# clk_gate.net
KiCad netlist of a schematic drawn in EAGLE
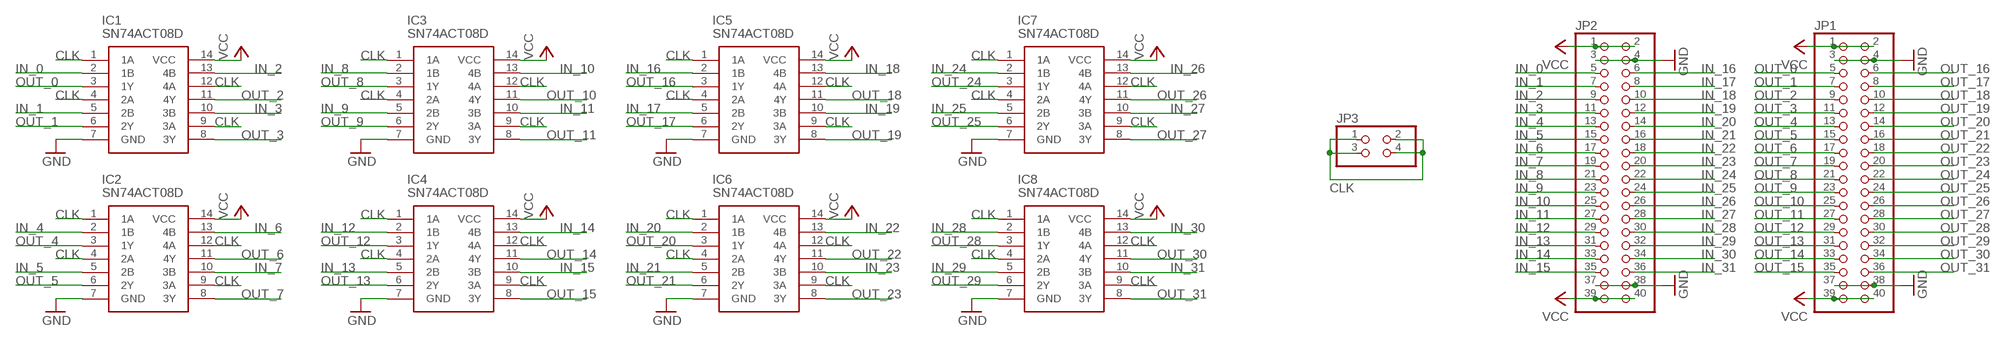
[diagram p0: schematic, sheet 1]

(export (version "E")
  (design (tool "Eeschema 10.0.6"))
  (components
    (comp (ref "IC1")
      (value "SN74ACT08D")
      (footprint "eagle-import:SOIC127P600X175-14N")
      (fields (field (name "MOUSER_PART_NUMBER") "595-SN74ACT08D"))
      (libsource (lib "eagle-import") (part "SN74ACT08D"))
    )
    (comp (ref "IC2")
      (value "SN74ACT08D")
      (footprint "eagle-import:SOIC127P600X175-14N")
      (fields (field (name "MOUSER_PART_NUMBER") "595-SN74ACT08D"))
      (libsource (lib "eagle-import") (part "SN74ACT08D"))
    )
    (comp (ref "IC3")
      (value "SN74ACT08D")
      (footprint "eagle-import:SOIC127P600X175-14N")
      (fields (field (name "MOUSER_PART_NUMBER") "595-SN74ACT08D"))
      (libsource (lib "eagle-import") (part "SN74ACT08D"))
    )
    (comp (ref "IC4")
      (value "SN74ACT08D")
      (footprint "eagle-import:SOIC127P600X175-14N")
      (fields (field (name "MOUSER_PART_NUMBER") "595-SN74ACT08D"))
      (libsource (lib "eagle-import") (part "SN74ACT08D"))
    )
    (comp (ref "IC5")
      (value "SN74ACT08D")
      (footprint "eagle-import:SOIC127P600X175-14N")
      (fields (field (name "MOUSER_PART_NUMBER") "595-SN74ACT08D"))
      (libsource (lib "eagle-import") (part "SN74ACT08D"))
    )
    (comp (ref "IC6")
      (value "SN74ACT08D")
      (footprint "eagle-import:SOIC127P600X175-14N")
      (fields (field (name "MOUSER_PART_NUMBER") "595-SN74ACT08D"))
      (libsource (lib "eagle-import") (part "SN74ACT08D"))
    )
    (comp (ref "IC7")
      (value "SN74ACT08D")
      (footprint "eagle-import:SOIC127P600X175-14N")
      (fields (field (name "MOUSER_PART_NUMBER") "595-SN74ACT08D"))
      (libsource (lib "eagle-import") (part "SN74ACT08D"))
    )
    (comp (ref "IC8")
      (value "SN74ACT08D")
      (footprint "eagle-import:SOIC127P600X175-14N")
      (fields (field (name "MOUSER_PART_NUMBER") "595-SN74ACT08D"))
      (libsource (lib "eagle-import") (part "SN74ACT08D"))
    )
    (comp (ref "JP1")
      (value "PINHD-2X20")
      (footprint "eagle-import:2X20")
      (libsource (lib "eagle-import") (part "PINHD-2X20"))
    )
    (comp (ref "JP2")
      (value "PINHD-2X20")
      (footprint "eagle-import:2X20")
      (libsource (lib "eagle-import") (part "PINHD-2X20"))
    )
    (comp (ref "JP3")
      (value "PINHD-2X2")
      (footprint "eagle-import:2X02")
      (libsource (lib "eagle-import") (part "PINHD-2X2"))
    )
  )
  (nets
    (net (code "1") (name "/CLK") (class "Default")
      (node (ref "IC1") (pin "1") (pinfunction "1A_1") (pintype "bidirectional"))
      (node (ref "IC1") (pin "12") (pinfunction "4A_12") (pintype "bidirectional"))
      (node (ref "IC1") (pin "4") (pinfunction "2A_4") (pintype "bidirectional"))
      (node (ref "IC1") (pin "9") (pinfunction "3A_9") (pintype "bidirectional"))
      (node (ref "IC2") (pin "1") (pinfunction "1A_1") (pintype "bidirectional"))
      (node (ref "IC2") (pin "12") (pinfunction "4A_12") (pintype "bidirectional"))
      (node (ref "IC2") (pin "4") (pinfunction "2A_4") (pintype "bidirectional"))
      (node (ref "IC2") (pin "9") (pinfunction "3A_9") (pintype "bidirectional"))
      (node (ref "IC3") (pin "1") (pinfunction "1A_1") (pintype "bidirectional"))
      (node (ref "IC3") (pin "12") (pinfunction "4A_12") (pintype "bidirectional"))
      (node (ref "IC3") (pin "4") (pinfunction "2A_4") (pintype "bidirectional"))
      (node (ref "IC3") (pin "9") (pinfunction "3A_9") (pintype "bidirectional"))
      (node (ref "IC4") (pin "1") (pinfunction "1A_1") (pintype "bidirectional"))
      (node (ref "IC4") (pin "12") (pinfunction "4A_12") (pintype "bidirectional"))
      (node (ref "IC4") (pin "4") (pinfunction "2A_4") (pintype "bidirectional"))
      (node (ref "IC4") (pin "9") (pinfunction "3A_9") (pintype "bidirectional"))
      (node (ref "IC5") (pin "1") (pinfunction "1A_1") (pintype "bidirectional"))
      (node (ref "IC5") (pin "12") (pinfunction "4A_12") (pintype "bidirectional"))
      (node (ref "IC5") (pin "4") (pinfunction "2A_4") (pintype "bidirectional"))
      (node (ref "IC5") (pin "9") (pinfunction "3A_9") (pintype "bidirectional"))
      (node (ref "IC6") (pin "1") (pinfunction "1A_1") (pintype "bidirectional"))
      (node (ref "IC6") (pin "12") (pinfunction "4A_12") (pintype "bidirectional"))
      (node (ref "IC6") (pin "4") (pinfunction "2A_4") (pintype "bidirectional"))
      (node (ref "IC6") (pin "9") (pinfunction "3A_9") (pintype "bidirectional"))
      (node (ref "IC7") (pin "1") (pinfunction "1A_1") (pintype "bidirectional"))
      (node (ref "IC7") (pin "12") (pinfunction "4A_12") (pintype "bidirectional"))
      (node (ref "IC7") (pin "4") (pinfunction "2A_4") (pintype "bidirectional"))
      (node (ref "IC7") (pin "9") (pinfunction "3A_9") (pintype "bidirectional"))
      (node (ref "IC8") (pin "1") (pinfunction "1A_1") (pintype "bidirectional"))
      (node (ref "IC8") (pin "12") (pinfunction "4A_12") (pintype "bidirectional"))
      (node (ref "IC8") (pin "4") (pinfunction "2A_4") (pintype "bidirectional"))
      (node (ref "IC8") (pin "9") (pinfunction "3A_9") (pintype "bidirectional"))
      (node (ref "JP3") (pin "1") (pinfunction "1_1") (pintype "passive"))
      (node (ref "JP3") (pin "2") (pinfunction "2_2") (pintype "passive"))
      (node (ref "JP3") (pin "3") (pinfunction "3_3") (pintype "passive"))
      (node (ref "JP3") (pin "4") (pinfunction "4_4") (pintype "passive"))
    )
    (net (code "2") (name "/IN_0") (class "Default")
      (node (ref "IC1") (pin "2") (pinfunction "1B_2") (pintype "bidirectional"))
      (node (ref "JP2") (pin "5") (pinfunction "5_5") (pintype "passive"))
    )
    (net (code "3") (name "/IN_1") (class "Default")
      (node (ref "IC1") (pin "5") (pinfunction "2B_5") (pintype "bidirectional"))
      (node (ref "JP2") (pin "7") (pinfunction "7_7") (pintype "passive"))
    )
    (net (code "4") (name "/IN_2") (class "Default")
      (node (ref "IC1") (pin "13") (pinfunction "4B_13") (pintype "bidirectional"))
      (node (ref "JP2") (pin "9") (pinfunction "9_9") (pintype "passive"))
    )
    (net (code "5") (name "/IN_3") (class "Default")
      (node (ref "IC1") (pin "10") (pinfunction "3B_10") (pintype "bidirectional"))
      (node (ref "JP2") (pin "11") (pinfunction "11_11") (pintype "passive"))
    )
    (net (code "6") (name "/IN_4") (class "Default")
      (node (ref "IC2") (pin "2") (pinfunction "1B_2") (pintype "bidirectional"))
      (node (ref "JP2") (pin "13") (pinfunction "13_13") (pintype "passive"))
    )
    (net (code "7") (name "/IN_5") (class "Default")
      (node (ref "IC2") (pin "5") (pinfunction "2B_5") (pintype "bidirectional"))
      (node (ref "JP2") (pin "15") (pinfunction "15_15") (pintype "passive"))
    )
    (net (code "8") (name "/IN_6") (class "Default")
      (node (ref "IC2") (pin "13") (pinfunction "4B_13") (pintype "bidirectional"))
      (node (ref "JP2") (pin "17") (pinfunction "17_17") (pintype "passive"))
    )
    (net (code "9") (name "/IN_7") (class "Default")
      (node (ref "IC2") (pin "10") (pinfunction "3B_10") (pintype "bidirectional"))
      (node (ref "JP2") (pin "19") (pinfunction "19_19") (pintype "passive"))
    )
    (net (code "10") (name "/IN_8") (class "Default")
      (node (ref "IC3") (pin "2") (pinfunction "1B_2") (pintype "bidirectional"))
      (node (ref "JP2") (pin "21") (pinfunction "21_21") (pintype "passive"))
    )
    (net (code "11") (name "/IN_9") (class "Default")
      (node (ref "IC3") (pin "5") (pinfunction "2B_5") (pintype "bidirectional"))
      (node (ref "JP2") (pin "23") (pinfunction "23_23") (pintype "passive"))
    )
    (net (code "12") (name "/IN_10") (class "Default")
      (node (ref "IC3") (pin "13") (pinfunction "4B_13") (pintype "bidirectional"))
      (node (ref "JP2") (pin "25") (pinfunction "25_25") (pintype "passive"))
    )
    (net (code "13") (name "/IN_11") (class "Default")
      (node (ref "IC3") (pin "10") (pinfunction "3B_10") (pintype "bidirectional"))
      (node (ref "JP2") (pin "27") (pinfunction "27_27") (pintype "passive"))
    )
    (net (code "14") (name "/IN_12") (class "Default")
      (node (ref "IC4") (pin "2") (pinfunction "1B_2") (pintype "bidirectional"))
      (node (ref "JP2") (pin "29") (pinfunction "29_29") (pintype "passive"))
    )
    (net (code "15") (name "/IN_13") (class "Default")
      (node (ref "IC4") (pin "5") (pinfunction "2B_5") (pintype "bidirectional"))
      (node (ref "JP2") (pin "31") (pinfunction "31_31") (pintype "passive"))
    )
    (net (code "16") (name "/IN_14") (class "Default")
      (node (ref "IC4") (pin "13") (pinfunction "4B_13") (pintype "bidirectional"))
      (node (ref "JP2") (pin "33") (pinfunction "33_33") (pintype "passive"))
    )
    (net (code "17") (name "/IN_15") (class "Default")
      (node (ref "IC4") (pin "10") (pinfunction "3B_10") (pintype "bidirectional"))
      (node (ref "JP2") (pin "35") (pinfunction "35_35") (pintype "passive"))
    )
    (net (code "18") (name "/IN_16") (class "Default")
      (node (ref "IC5") (pin "2") (pinfunction "1B_2") (pintype "bidirectional"))
      (node (ref "JP2") (pin "6") (pinfunction "6_6") (pintype "passive"))
    )
    (net (code "19") (name "/IN_17") (class "Default")
      (node (ref "IC5") (pin "5") (pinfunction "2B_5") (pintype "bidirectional"))
      (node (ref "JP2") (pin "8") (pinfunction "8_8") (pintype "passive"))
    )
    (net (code "20") (name "/IN_18") (class "Default")
      (node (ref "IC5") (pin "13") (pinfunction "4B_13") (pintype "bidirectional"))
      (node (ref "JP2") (pin "10") (pinfunction "10_10") (pintype "passive"))
    )
    (net (code "21") (name "/IN_19") (class "Default")
      (node (ref "IC5") (pin "10") (pinfunction "3B_10") (pintype "bidirectional"))
      (node (ref "JP2") (pin "12") (pinfunction "12_12") (pintype "passive"))
    )
    (net (code "22") (name "/IN_20") (class "Default")
      (node (ref "IC6") (pin "2") (pinfunction "1B_2") (pintype "bidirectional"))
      (node (ref "JP2") (pin "14") (pinfunction "14_14") (pintype "passive"))
    )
    (net (code "23") (name "/IN_21") (class "Default")
      (node (ref "IC6") (pin "5") (pinfunction "2B_5") (pintype "bidirectional"))
      (node (ref "JP2") (pin "16") (pinfunction "16_16") (pintype "passive"))
    )
    (net (code "24") (name "/IN_22") (class "Default")
      (node (ref "IC6") (pin "13") (pinfunction "4B_13") (pintype "bidirectional"))
      (node (ref "JP2") (pin "18") (pinfunction "18_18") (pintype "passive"))
    )
    (net (code "25") (name "/IN_23") (class "Default")
      (node (ref "IC6") (pin "10") (pinfunction "3B_10") (pintype "bidirectional"))
      (node (ref "JP2") (pin "20") (pinfunction "20_20") (pintype "passive"))
    )
    (net (code "26") (name "/IN_24") (class "Default")
      (node (ref "IC7") (pin "2") (pinfunction "1B_2") (pintype "bidirectional"))
      (node (ref "JP2") (pin "22") (pinfunction "22_22") (pintype "passive"))
    )
    (net (code "27") (name "/IN_25") (class "Default")
      (node (ref "IC7") (pin "5") (pinfunction "2B_5") (pintype "bidirectional"))
      (node (ref "JP2") (pin "24") (pinfunction "24_24") (pintype "passive"))
    )
    (net (code "28") (name "/IN_26") (class "Default")
      (node (ref "IC7") (pin "13") (pinfunction "4B_13") (pintype "bidirectional"))
      (node (ref "JP2") (pin "26") (pinfunction "26_26") (pintype "passive"))
    )
    (net (code "29") (name "/IN_27") (class "Default")
      (node (ref "IC7") (pin "10") (pinfunction "3B_10") (pintype "bidirectional"))
      (node (ref "JP2") (pin "28") (pinfunction "28_28") (pintype "passive"))
    )
    (net (code "30") (name "/IN_28") (class "Default")
      (node (ref "IC8") (pin "2") (pinfunction "1B_2") (pintype "bidirectional"))
      (node (ref "JP2") (pin "30") (pinfunction "30_30") (pintype "passive"))
    )
    (net (code "31") (name "/IN_29") (class "Default")
      (node (ref "IC8") (pin "5") (pinfunction "2B_5") (pintype "bidirectional"))
      (node (ref "JP2") (pin "32") (pinfunction "32_32") (pintype "passive"))
    )
    (net (code "32") (name "/IN_30") (class "Default")
      (node (ref "IC8") (pin "13") (pinfunction "4B_13") (pintype "bidirectional"))
      (node (ref "JP2") (pin "34") (pinfunction "34_34") (pintype "passive"))
    )
    (net (code "33") (name "/IN_31") (class "Default")
      (node (ref "IC8") (pin "10") (pinfunction "3B_10") (pintype "bidirectional"))
      (node (ref "JP2") (pin "36") (pinfunction "36_36") (pintype "passive"))
    )
    (net (code "34") (name "/OUT_0") (class "Default")
      (node (ref "IC1") (pin "3") (pinfunction "1Y_3") (pintype "bidirectional"))
      (node (ref "JP1") (pin "5") (pinfunction "5_5") (pintype "passive"))
    )
    (net (code "35") (name "/OUT_1") (class "Default")
      (node (ref "IC1") (pin "6") (pinfunction "2Y_6") (pintype "bidirectional"))
      (node (ref "JP1") (pin "7") (pinfunction "7_7") (pintype "passive"))
    )
    (net (code "36") (name "/OUT_2") (class "Default")
      (node (ref "IC1") (pin "11") (pinfunction "4Y_11") (pintype "bidirectional"))
      (node (ref "JP1") (pin "9") (pinfunction "9_9") (pintype "passive"))
    )
    (net (code "37") (name "/OUT_3") (class "Default")
      (node (ref "IC1") (pin "8") (pinfunction "3Y_8") (pintype "bidirectional"))
      (node (ref "JP1") (pin "11") (pinfunction "11_11") (pintype "passive"))
    )
    (net (code "38") (name "/OUT_4") (class "Default")
      (node (ref "IC2") (pin "3") (pinfunction "1Y_3") (pintype "bidirectional"))
      (node (ref "JP1") (pin "13") (pinfunction "13_13") (pintype "passive"))
    )
    (net (code "39") (name "/OUT_5") (class "Default")
      (node (ref "IC2") (pin "6") (pinfunction "2Y_6") (pintype "bidirectional"))
      (node (ref "JP1") (pin "15") (pinfunction "15_15") (pintype "passive"))
    )
    (net (code "40") (name "/OUT_6") (class "Default")
      (node (ref "IC2") (pin "11") (pinfunction "4Y_11") (pintype "bidirectional"))
      (node (ref "JP1") (pin "17") (pinfunction "17_17") (pintype "passive"))
    )
    (net (code "41") (name "/OUT_7") (class "Default")
      (node (ref "IC2") (pin "8") (pinfunction "3Y_8") (pintype "bidirectional"))
      (node (ref "JP1") (pin "19") (pinfunction "19_19") (pintype "passive"))
    )
    (net (code "42") (name "/OUT_8") (class "Default")
      (node (ref "IC3") (pin "3") (pinfunction "1Y_3") (pintype "bidirectional"))
      (node (ref "JP1") (pin "21") (pinfunction "21_21") (pintype "passive"))
    )
    (net (code "43") (name "/OUT_9") (class "Default")
      (node (ref "IC3") (pin "6") (pinfunction "2Y_6") (pintype "bidirectional"))
      (node (ref "JP1") (pin "23") (pinfunction "23_23") (pintype "passive"))
    )
    (net (code "44") (name "/OUT_10") (class "Default")
      (node (ref "IC3") (pin "11") (pinfunction "4Y_11") (pintype "bidirectional"))
      (node (ref "JP1") (pin "25") (pinfunction "25_25") (pintype "passive"))
    )
    (net (code "45") (name "/OUT_11") (class "Default")
      (node (ref "IC3") (pin "8") (pinfunction "3Y_8") (pintype "bidirectional"))
      (node (ref "JP1") (pin "27") (pinfunction "27_27") (pintype "passive"))
    )
    (net (code "46") (name "/OUT_12") (class "Default")
      (node (ref "IC4") (pin "3") (pinfunction "1Y_3") (pintype "bidirectional"))
      (node (ref "JP1") (pin "29") (pinfunction "29_29") (pintype "passive"))
    )
    (net (code "47") (name "/OUT_13") (class "Default")
      (node (ref "IC4") (pin "6") (pinfunction "2Y_6") (pintype "bidirectional"))
      (node (ref "JP1") (pin "31") (pinfunction "31_31") (pintype "passive"))
    )
    (net (code "48") (name "/OUT_14") (class "Default")
      (node (ref "IC4") (pin "11") (pinfunction "4Y_11") (pintype "bidirectional"))
      (node (ref "JP1") (pin "33") (pinfunction "33_33") (pintype "passive"))
    )
    (net (code "49") (name "/OUT_15") (class "Default")
      (node (ref "IC4") (pin "8") (pinfunction "3Y_8") (pintype "bidirectional"))
      (node (ref "JP1") (pin "35") (pinfunction "35_35") (pintype "passive"))
    )
    (net (code "50") (name "/OUT_16") (class "Default")
      (node (ref "IC5") (pin "3") (pinfunction "1Y_3") (pintype "bidirectional"))
      (node (ref "JP1") (pin "6") (pinfunction "6_6") (pintype "passive"))
    )
    (net (code "51") (name "/OUT_17") (class "Default")
      (node (ref "IC5") (pin "6") (pinfunction "2Y_6") (pintype "bidirectional"))
      (node (ref "JP1") (pin "8") (pinfunction "8_8") (pintype "passive"))
    )
    (net (code "52") (name "/OUT_18") (class "Default")
      (node (ref "IC5") (pin "11") (pinfunction "4Y_11") (pintype "bidirectional"))
      (node (ref "JP1") (pin "10") (pinfunction "10_10") (pintype "passive"))
    )
    (net (code "53") (name "/OUT_19") (class "Default")
      (node (ref "IC5") (pin "8") (pinfunction "3Y_8") (pintype "bidirectional"))
      (node (ref "JP1") (pin "12") (pinfunction "12_12") (pintype "passive"))
    )
    (net (code "54") (name "/OUT_20") (class "Default")
      (node (ref "IC6") (pin "3") (pinfunction "1Y_3") (pintype "bidirectional"))
      (node (ref "JP1") (pin "14") (pinfunction "14_14") (pintype "passive"))
    )
    (net (code "55") (name "/OUT_21") (class "Default")
      (node (ref "IC6") (pin "6") (pinfunction "2Y_6") (pintype "bidirectional"))
      (node (ref "JP1") (pin "16") (pinfunction "16_16") (pintype "passive"))
    )
    (net (code "56") (name "/OUT_22") (class "Default")
      (node (ref "IC6") (pin "11") (pinfunction "4Y_11") (pintype "bidirectional"))
      (node (ref "JP1") (pin "18") (pinfunction "18_18") (pintype "passive"))
    )
    (net (code "57") (name "/OUT_23") (class "Default")
      (node (ref "IC6") (pin "8") (pinfunction "3Y_8") (pintype "bidirectional"))
      (node (ref "JP1") (pin "20") (pinfunction "20_20") (pintype "passive"))
    )
    (net (code "58") (name "/OUT_24") (class "Default")
      (node (ref "IC7") (pin "3") (pinfunction "1Y_3") (pintype "bidirectional"))
      (node (ref "JP1") (pin "22") (pinfunction "22_22") (pintype "passive"))
    )
    (net (code "59") (name "/OUT_25") (class "Default")
      (node (ref "IC7") (pin "6") (pinfunction "2Y_6") (pintype "bidirectional"))
      (node (ref "JP1") (pin "24") (pinfunction "24_24") (pintype "passive"))
    )
    (net (code "60") (name "/OUT_26") (class "Default")
      (node (ref "IC7") (pin "11") (pinfunction "4Y_11") (pintype "bidirectional"))
      (node (ref "JP1") (pin "26") (pinfunction "26_26") (pintype "passive"))
    )
    (net (code "61") (name "/OUT_27") (class "Default")
      (node (ref "IC7") (pin "8") (pinfunction "3Y_8") (pintype "bidirectional"))
      (node (ref "JP1") (pin "28") (pinfunction "28_28") (pintype "passive"))
    )
    (net (code "62") (name "/OUT_28") (class "Default")
      (node (ref "IC8") (pin "3") (pinfunction "1Y_3") (pintype "bidirectional"))
      (node (ref "JP1") (pin "30") (pinfunction "30_30") (pintype "passive"))
    )
    (net (code "63") (name "/OUT_29") (class "Default")
      (node (ref "IC8") (pin "6") (pinfunction "2Y_6") (pintype "bidirectional"))
      (node (ref "JP1") (pin "32") (pinfunction "32_32") (pintype "passive"))
    )
    (net (code "64") (name "/OUT_30") (class "Default")
      (node (ref "IC8") (pin "11") (pinfunction "4Y_11") (pintype "bidirectional"))
      (node (ref "JP1") (pin "34") (pinfunction "34_34") (pintype "passive"))
    )
    (net (code "65") (name "/OUT_31") (class "Default")
      (node (ref "IC8") (pin "8") (pinfunction "3Y_8") (pintype "bidirectional"))
      (node (ref "JP1") (pin "36") (pinfunction "36_36") (pintype "passive"))
    )
    (net (code "66") (name "GND") (class "Default")
      (node (ref "IC1") (pin "7") (pinfunction "GND_7") (pintype "bidirectional"))
      (node (ref "IC2") (pin "7") (pinfunction "GND_7") (pintype "bidirectional"))
      (node (ref "IC3") (pin "7") (pinfunction "GND_7") (pintype "bidirectional"))
      (node (ref "IC4") (pin "7") (pinfunction "GND_7") (pintype "bidirectional"))
      (node (ref "IC5") (pin "7") (pinfunction "GND_7") (pintype "bidirectional"))
      (node (ref "IC6") (pin "7") (pinfunction "GND_7") (pintype "bidirectional"))
      (node (ref "IC7") (pin "7") (pinfunction "GND_7") (pintype "bidirectional"))
      (node (ref "IC8") (pin "7") (pinfunction "GND_7") (pintype "bidirectional"))
      (node (ref "JP1") (pin "3") (pinfunction "3_3") (pintype "passive"))
      (node (ref "JP1") (pin "37") (pinfunction "37_37") (pintype "passive"))
      (node (ref "JP1") (pin "38") (pinfunction "38_38") (pintype "passive"))
      (node (ref "JP1") (pin "4") (pinfunction "4_4") (pintype "passive"))
      (node (ref "JP2") (pin "3") (pinfunction "3_3") (pintype "passive"))
      (node (ref "JP2") (pin "37") (pinfunction "37_37") (pintype "passive"))
      (node (ref "JP2") (pin "38") (pinfunction "38_38") (pintype "passive"))
      (node (ref "JP2") (pin "4") (pinfunction "4_4") (pintype "passive"))
    )
    (net (code "67") (name "VCC") (class "Default")
      (node (ref "IC1") (pin "14") (pinfunction "VCC_14") (pintype "bidirectional"))
      (node (ref "IC2") (pin "14") (pinfunction "VCC_14") (pintype "bidirectional"))
      (node (ref "IC3") (pin "14") (pinfunction "VCC_14") (pintype "bidirectional"))
      (node (ref "IC4") (pin "14") (pinfunction "VCC_14") (pintype "bidirectional"))
      (node (ref "IC5") (pin "14") (pinfunction "VCC_14") (pintype "bidirectional"))
      (node (ref "IC6") (pin "14") (pinfunction "VCC_14") (pintype "bidirectional"))
      (node (ref "IC7") (pin "14") (pinfunction "VCC_14") (pintype "bidirectional"))
      (node (ref "IC8") (pin "14") (pinfunction "VCC_14") (pintype "bidirectional"))
      (node (ref "JP1") (pin "1") (pinfunction "1_1") (pintype "passive"))
      (node (ref "JP1") (pin "2") (pinfunction "2_2") (pintype "passive"))
      (node (ref "JP1") (pin "39") (pinfunction "39_39") (pintype "passive"))
      (node (ref "JP1") (pin "40") (pinfunction "40_40") (pintype "passive"))
      (node (ref "JP2") (pin "1") (pinfunction "1_1") (pintype "passive"))
      (node (ref "JP2") (pin "2") (pinfunction "2_2") (pintype "passive"))
      (node (ref "JP2") (pin "39") (pinfunction "39_39") (pintype "passive"))
      (node (ref "JP2") (pin "40") (pinfunction "40_40") (pintype "passive"))
    )
  )
)
